# 1-Holberton_TOP.net
KiCad netlist of a schematic drawn in Altium Designer
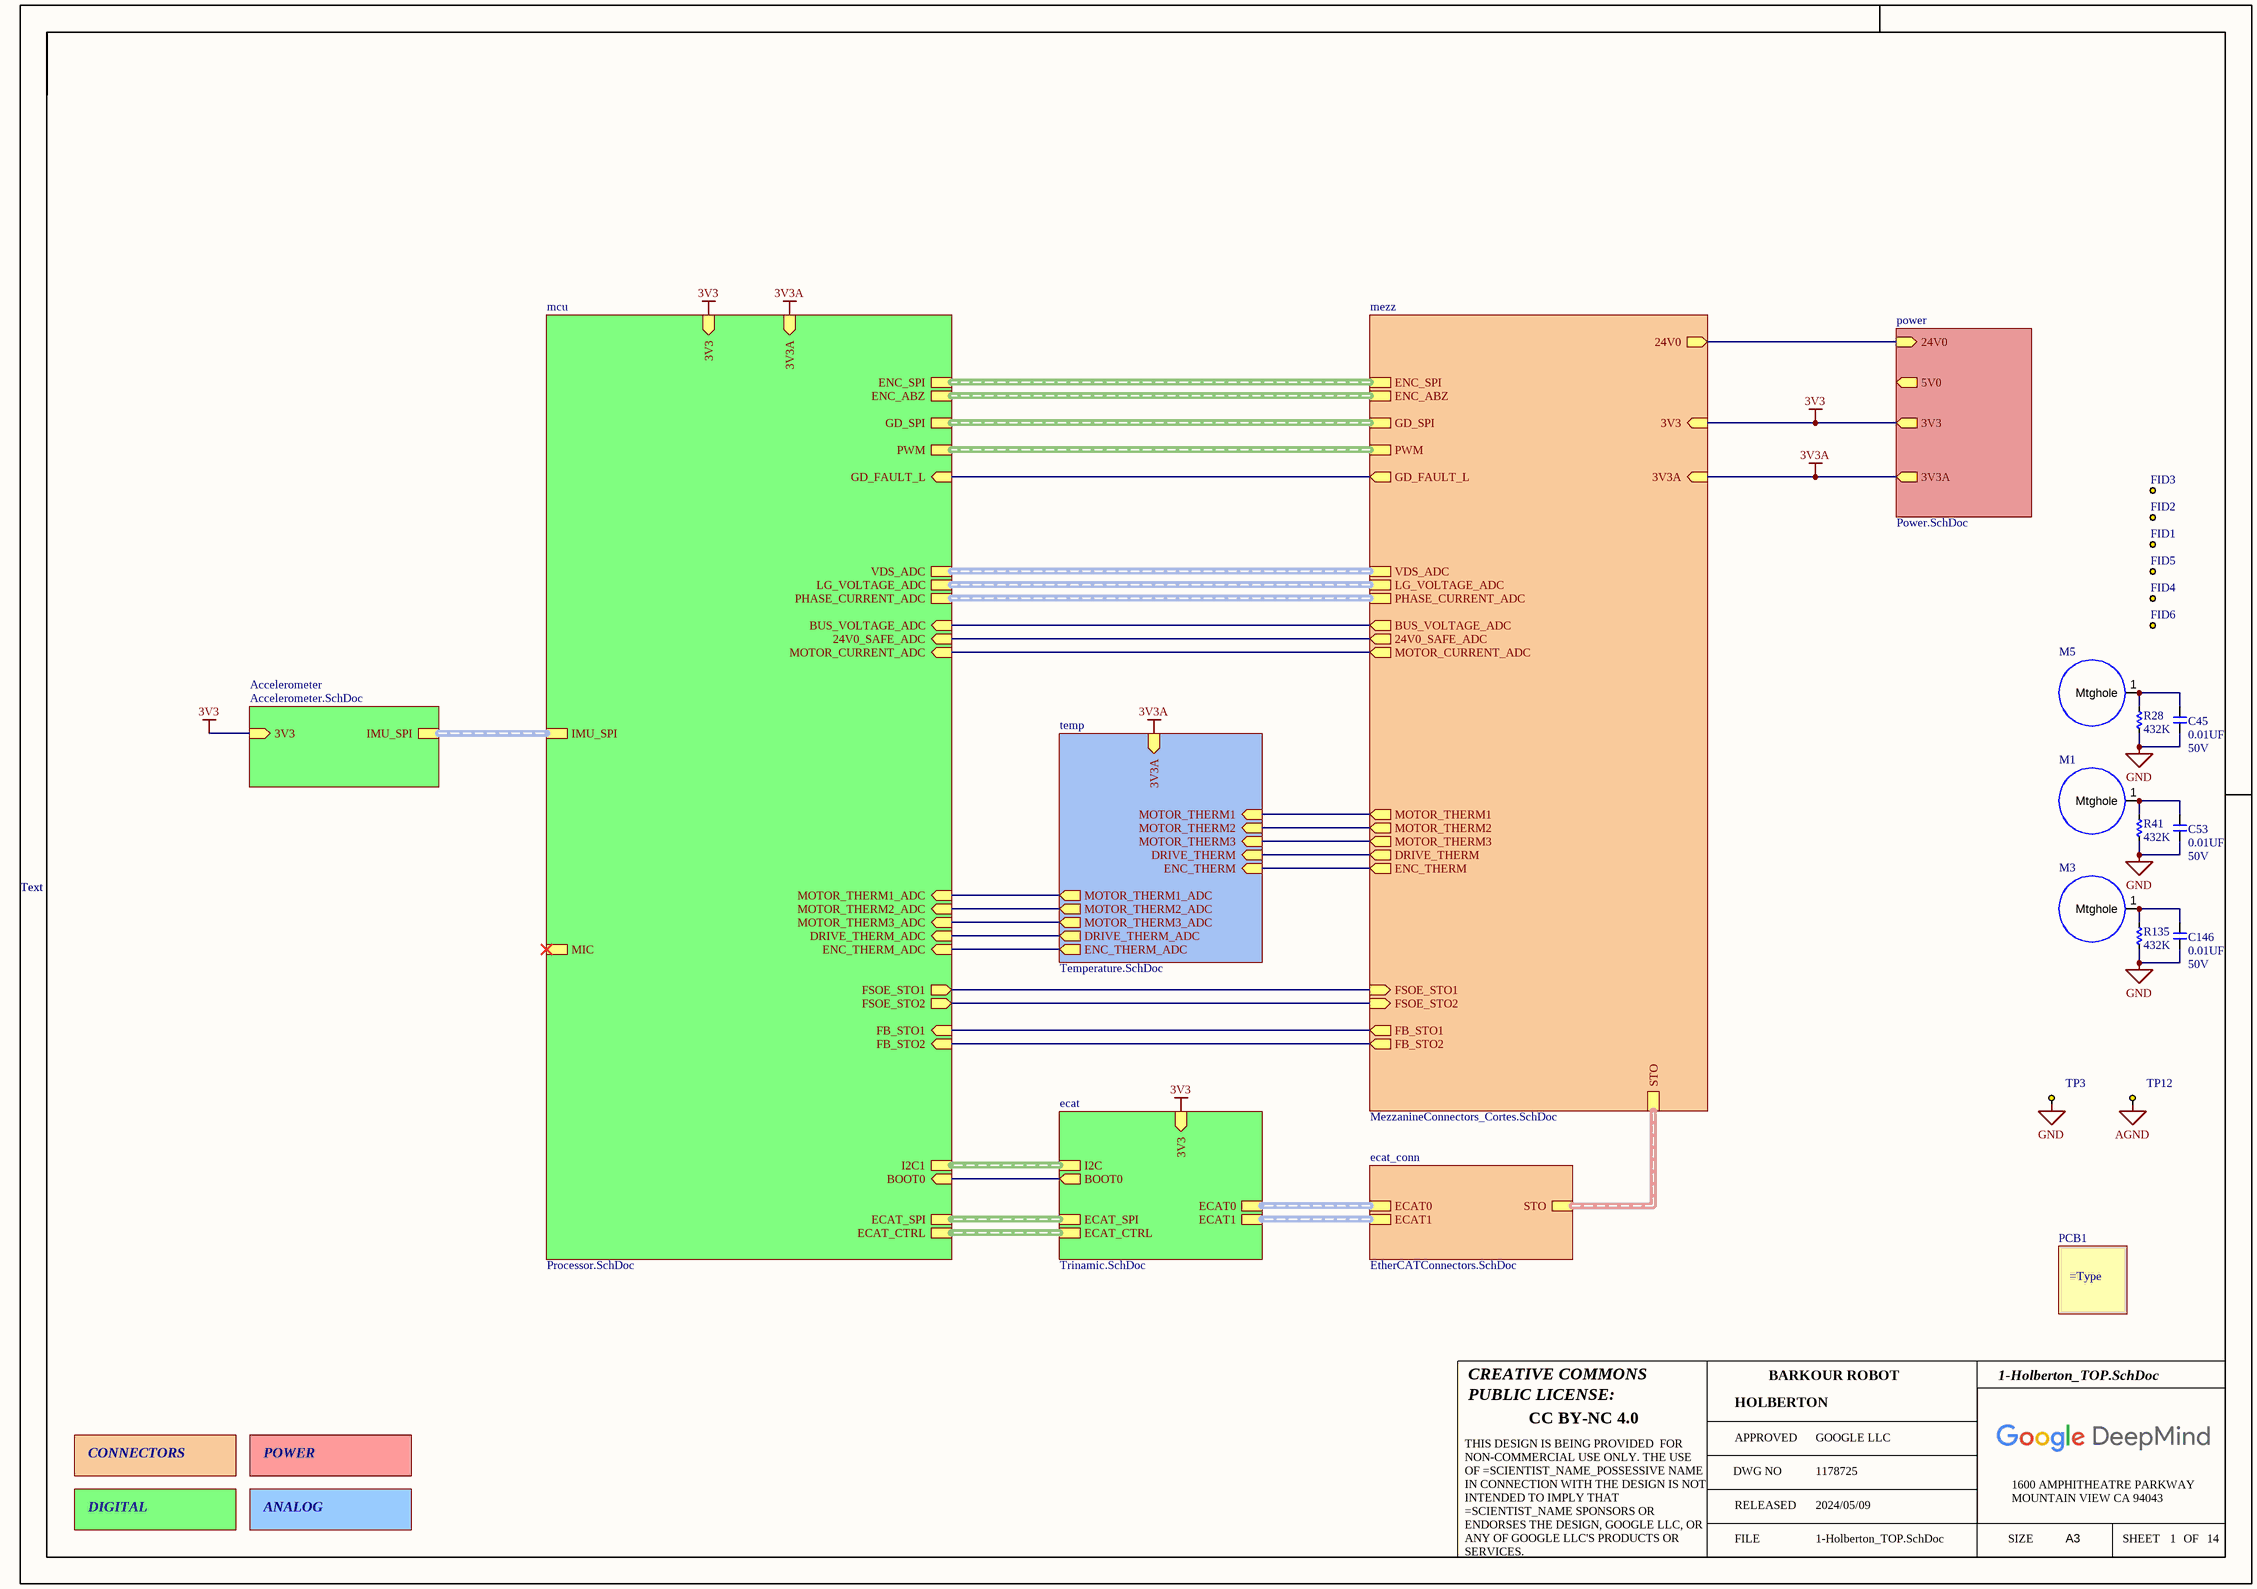
[diagram p0: 1-Holberton_TOP.SchDoc]

(export (version "E")
  (design (tool "Eeschema 10.0.6"))
  (components
    (comp (ref "C45")
      (value "0.01UF")
      (footprint "C0402")
      (description "CAP, CER, X7R, 0.01uF, 50V, 20%, 0402, 0.56mm T")
      (fields
        (field (name "MFG") "KEMET")
        (field (name "VOLTAGE") "50V")
        (field (name "Comment") "__Template_Cap")
      )
      (libsource (lib "AltiumReleaseLibDB") (part "__Template_Cap"))
    )
    (comp (ref "C53")
      (value "0.01UF")
      (footprint "C0402")
      (description "CAP, CER, X7R, 0.01uF, 50V, 20%, 0402, 0.56mm T")
      (fields
        (field (name "MFG") "KEMET")
        (field (name "VOLTAGE") "50V")
        (field (name "Comment") "__Template_Cap")
      )
      (libsource (lib "AltiumReleaseLibDB") (part "__Template_Cap"))
    )
    (comp (ref "C146")
      (value "0.01UF")
      (footprint "C0402")
      (description "CAP, CER, X7R, 0.01uF, 50V, 20%, 0402, 0.56mm T")
      (fields
        (field (name "MFG") "KEMET")
        (field (name "VOLTAGE") "50V")
        (field (name "Comment") "__Template_Cap")
      )
      (libsource (lib "AltiumReleaseLibDB") (part "__Template_Cap"))
    )
    (comp (ref "FID1")
      (value "FIDUCIAL")
      (footprint "FIDUCIAL_1MM")
      (description "FIDUCIAL 1MM COPPER CIRCLE 3MM MASK PULLBACK")
      (fields (field (name "MFG") "_PCB Feature"))
      (libsource (lib "AltiumReleaseLibDB") (part "FIDUCIAL"))
    )
    (comp (ref "FID2")
      (value "FIDUCIAL")
      (footprint "FIDUCIAL_1MM")
      (description "FIDUCIAL 1MM COPPER CIRCLE 3MM MASK PULLBACK")
      (fields (field (name "MFG") "_PCB Feature"))
      (libsource (lib "AltiumReleaseLibDB") (part "FIDUCIAL"))
    )
    (comp (ref "FID3")
      (value "FIDUCIAL")
      (footprint "FIDUCIAL_1MM")
      (description "FIDUCIAL 1MM COPPER CIRCLE 3MM MASK PULLBACK")
      (fields (field (name "MFG") "_PCB Feature"))
      (libsource (lib "AltiumReleaseLibDB") (part "FIDUCIAL"))
    )
    (comp (ref "FID4")
      (value "FIDUCIAL")
      (footprint "FIDUCIAL_1MM")
      (description "FIDUCIAL 1MM COPPER CIRCLE 3MM MASK PULLBACK")
      (fields (field (name "MFG") "_PCB Feature"))
      (libsource (lib "AltiumReleaseLibDB") (part "FIDUCIAL"))
    )
    (comp (ref "FID5")
      (value "FIDUCIAL")
      (footprint "FIDUCIAL_1MM")
      (description "FIDUCIAL 1MM COPPER CIRCLE 3MM MASK PULLBACK")
      (fields (field (name "MFG") "_PCB Feature"))
      (libsource (lib "AltiumReleaseLibDB") (part "FIDUCIAL"))
    )
    (comp (ref "FID6")
      (value "FIDUCIAL")
      (footprint "FIDUCIAL_1MM")
      (description "FIDUCIAL 1MM COPPER CIRCLE 3MM MASK PULLBACK")
      (fields (field (name "MFG") "_PCB Feature"))
      (libsource (lib "AltiumReleaseLibDB") (part "FIDUCIAL"))
    )
    (comp (ref "M1")
      (value "3.7mm hole 5mm pad")
      (footprint "3.7hole5pad")
      (libsource (lib "MiscSch1") (part "MtgHole"))
    )
    (comp (ref "M3")
      (value "3.7mm hole 5mm pad")
      (footprint "3.7hole5pad")
      (libsource (lib "MiscSch1") (part "MtgHole"))
    )
    (comp (ref "M5")
      (value "3.7mm hole 5mm pad")
      (footprint "3.7hole5pad")
      (libsource (lib "MiscSch1") (part "MtgHole"))
    )
    (comp (ref "PCB1") (value "~") (description "PCB") (libsource (lib "AltiumReleaseLibDB") (part "Label")))
    (comp (ref "R28")
      (value "432K")
      (footprint "R0402")
      (description "RES, 432K, 1%, 1/16W, 0402")
      (fields (field (name "MFG") "VISHAY"))
      (libsource (lib "AltiumReleaseLibDB") (part "__Template_Resistor"))
    )
    (comp (ref "R41")
      (value "432K")
      (footprint "R0402")
      (description "RES, 432K, 1%, 1/16W, 0402")
      (fields (field (name "MFG") "VISHAY"))
      (libsource (lib "AltiumReleaseLibDB") (part "__Template_Resistor"))
    )
    (comp (ref "R135")
      (value "432K")
      (footprint "R0402")
      (description "RES, 432K, 1%, 1/16W, 0402")
      (fields (field (name "MFG") "VISHAY"))
      (libsource (lib "AltiumReleaseLibDB") (part "__Template_Resistor"))
    )
    (comp (ref "TP3")
      (value "TEST_KEYSTONE5001")
      (footprint "TP_KEYSTONE_5001")
      (description "PC TEST POINT TH RING")
      (fields (field (name "MFG") "Keystone Electronics"))
      (libsource (lib "miscellaneous") (part "TEST_KEYSTONE5001"))
    )
    (comp (ref "TP12")
      (value "TEST_KEYSTONE5001")
      (footprint "TP_KEYSTONE_5001")
      (description "PC TEST POINT TH RING")
      (fields (field (name "MFG") "Keystone Electronics"))
      (libsource (lib "miscellaneous") (part "TEST_KEYSTONE5001"))
    )
  )
  (nets
    (net (code "39") (name "AGND") (class "Default") (node (ref "TP12") (pin "1") (pintype "passive")))
    (net (code "40") (name "GND") (class "Default")
      (node (ref "C146") (pin "2") (pintype "passive"))
      (node (ref "C45") (pin "2") (pintype "passive"))
      (node (ref "C53") (pin "2") (pintype "passive"))
      (node (ref "R135") (pin "1") (pintype "passive"))
      (node (ref "R28") (pin "1") (pintype "passive"))
      (node (ref "R41") (pin "1") (pintype "passive"))
      (node (ref "TP3") (pin "1") (pintype "passive"))
    )
    (net (code "41") (name "Net-(M1-Mtghole)") (class "Default")
      (node (ref "C53") (pin "1") (pintype "passive"))
      (node (ref "M1") (pin "1") (pinfunction "Mtghole_1") (pintype "passive"))
      (node (ref "R41") (pin "2") (pintype "passive"))
    )
    (net (code "42") (name "Net-(M3-Mtghole)") (class "Default")
      (node (ref "C146") (pin "1") (pintype "passive"))
      (node (ref "M3") (pin "1") (pinfunction "Mtghole_1") (pintype "passive"))
      (node (ref "R135") (pin "2") (pintype "passive"))
    )
    (net (code "43") (name "Net-(M5-Mtghole)") (class "Default")
      (node (ref "C45") (pin "1") (pintype "passive"))
      (node (ref "M5") (pin "1") (pinfunction "Mtghole_1") (pintype "passive"))
      (node (ref "R28") (pin "2") (pintype "passive"))
    )
  )
)
